# SCH_RAM-Module-Dual-IS66-DDR4_2026-05-29.net
KiCad netlist of a schematic drawn in EasyEDA
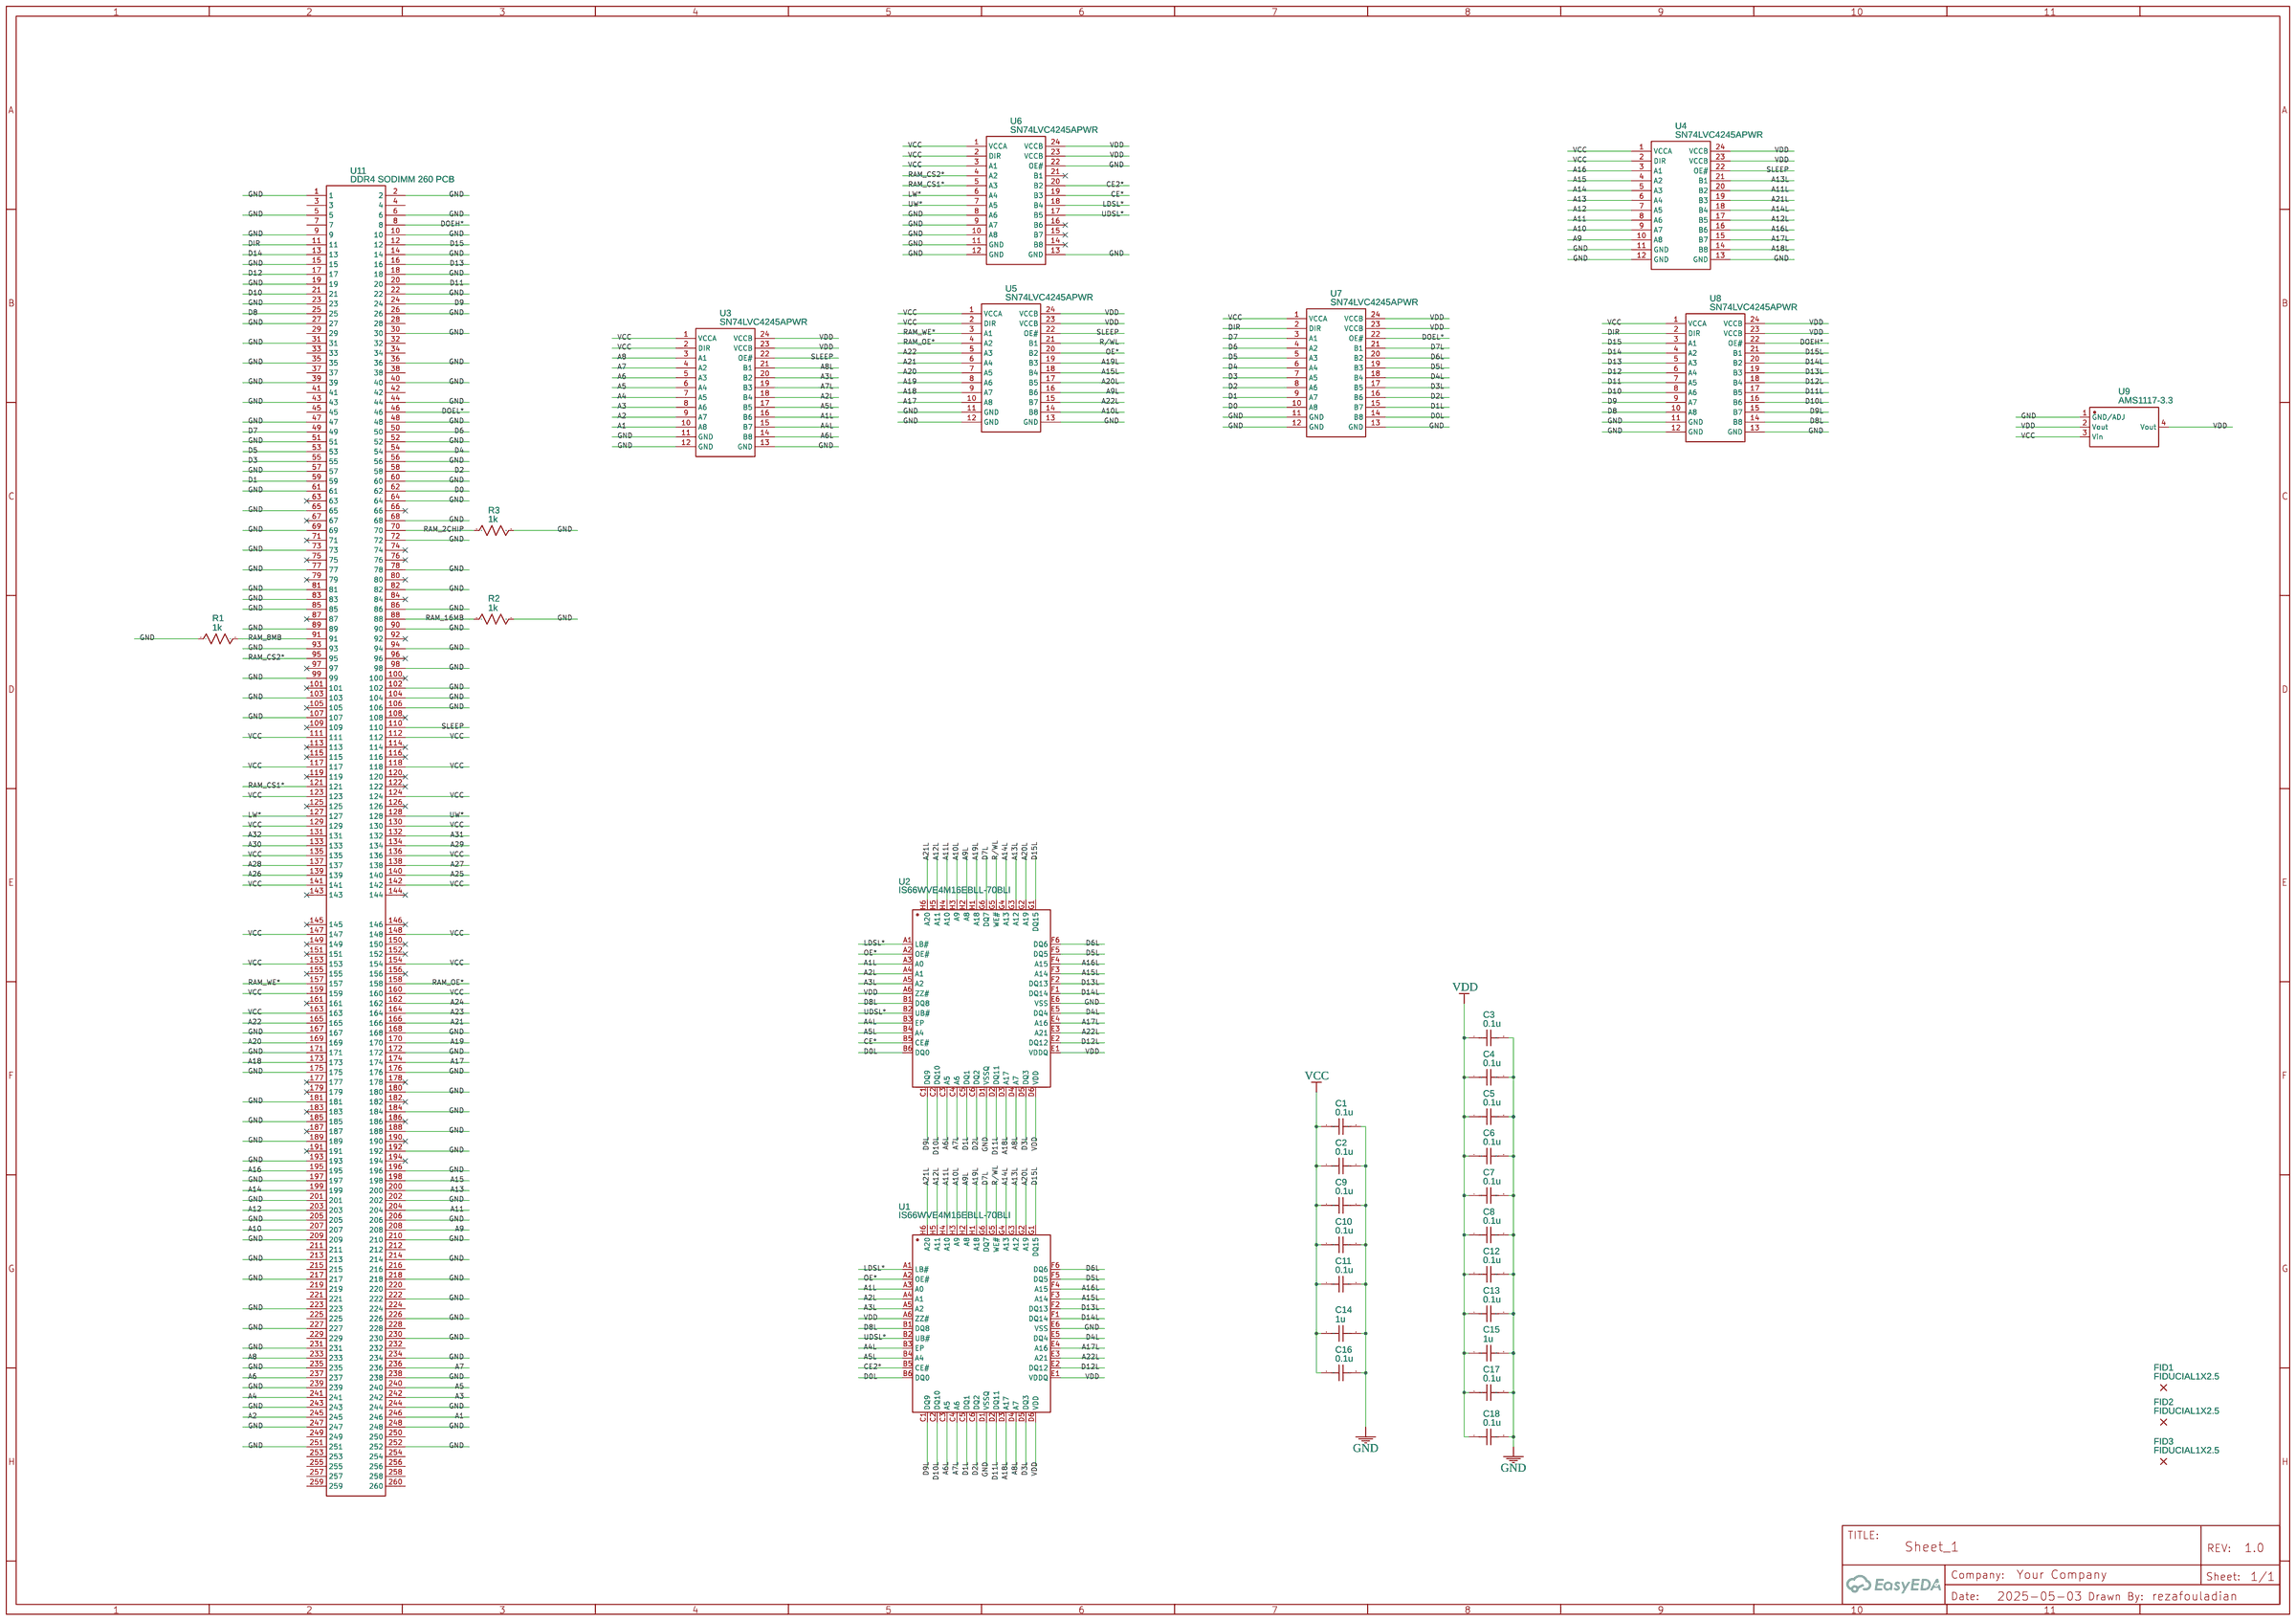
[diagram p0: schematic sheet]

(export (version "E")
  (design (tool "Eeschema 10.0.6"))
  (components
    (comp (ref "C1") (value "0.1u") (libsource (lib "") (part "C_0402_US")))
    (comp (ref "C2") (value "0.1u") (libsource (lib "") (part "C_0402_US")))
    (comp (ref "C3") (value "0.1u") (libsource (lib "") (part "C_0402_US")))
    (comp (ref "C4") (value "0.1u") (libsource (lib "") (part "C_0402_US")))
    (comp (ref "C5") (value "0.1u") (libsource (lib "") (part "C_0402_US")))
    (comp (ref "C6") (value "0.1u") (libsource (lib "") (part "C_0402_US")))
    (comp (ref "C7") (value "0.1u") (libsource (lib "") (part "C_0402_US")))
    (comp (ref "C8") (value "0.1u") (libsource (lib "") (part "C_0402_US")))
    (comp (ref "C9") (value "0.1u") (libsource (lib "") (part "C_0402_US")))
    (comp (ref "C10") (value "0.1u") (libsource (lib "") (part "C_0402_US")))
    (comp (ref "C11") (value "0.1u") (libsource (lib "") (part "C_0402_US")))
    (comp (ref "C12") (value "0.1u") (libsource (lib "") (part "C_0402_US")))
    (comp (ref "C13") (value "0.1u") (libsource (lib "") (part "C_0402_US")))
    (comp (ref "C14") (value "1u") (libsource (lib "") (part "C_0805_US")))
    (comp (ref "C15") (value "1u") (libsource (lib "") (part "C_0805_US")))
    (comp (ref "C16") (value "0.1u") (libsource (lib "") (part "C_0402_US")))
    (comp (ref "C17") (value "0.1u") (libsource (lib "") (part "C_0402_US")))
    (comp (ref "C18") (value "0.1u") (libsource (lib "") (part "C_0402_US")))
    (comp (ref "FID1") (value "FIDUCIAL1X2.5") (libsource (lib "") (part "FIDUCIAL1X2.5")))
    (comp (ref "FID2") (value "FIDUCIAL1X2.5") (libsource (lib "") (part "FIDUCIAL1X2.5")))
    (comp (ref "FID3") (value "FIDUCIAL1X2.5") (libsource (lib "") (part "FIDUCIAL1X2.5")))
    (comp (ref "R1") (value "1k") (libsource (lib "") (part "R_0402_US")))
    (comp (ref "R2") (value "1k") (libsource (lib "") (part "R_0402_US")))
    (comp (ref "R3") (value "1k") (libsource (lib "") (part "R_0402_US")))
    (comp (ref "U1")
      (value "IS66WVE4M16EBLL-70BLI")
      (fields (field (name "Manufacturer") "ISSI(美国芯成)"))
      (libsource (lib "") (part "IS66WVE4M16EBLL-70BLI"))
    )
    (comp (ref "U2")
      (value "IS66WVE4M16EBLL-70BLI")
      (fields (field (name "Manufacturer") "ISSI(美国芯成)"))
      (libsource (lib "") (part "IS66WVE4M16EBLL-70BLI"))
    )
    (comp (ref "U3")
      (value "SN74LVC4245APWR")
      (fields (field (name "Manufacturer") "TI(德州仪器)"))
      (libsource (lib "") (part "SN74LVC4245APWR"))
    )
    (comp (ref "U4")
      (value "SN74LVC4245APWR")
      (fields (field (name "Manufacturer") "TI(德州仪器)"))
      (libsource (lib "") (part "SN74LVC4245APWR"))
    )
    (comp (ref "U5")
      (value "SN74LVC4245APWR")
      (fields (field (name "Manufacturer") "TI(德州仪器)"))
      (libsource (lib "") (part "SN74LVC4245APWR"))
    )
    (comp (ref "U6")
      (value "SN74LVC4245APWR")
      (fields (field (name "Manufacturer") "TI(德州仪器)"))
      (libsource (lib "") (part "SN74LVC4245APWR"))
    )
    (comp (ref "U7")
      (value "SN74LVC4245APWR")
      (fields (field (name "Manufacturer") "TI(德州仪器)"))
      (libsource (lib "") (part "SN74LVC4245APWR"))
    )
    (comp (ref "U8")
      (value "SN74LVC4245APWR")
      (fields (field (name "Manufacturer") "TI(德州仪器)"))
      (libsource (lib "") (part "SN74LVC4245APWR"))
    )
    (comp (ref "U9")
      (value "AMS1117-3.3")
      (fields (field (name "Manufacturer") "AMS"))
      (libsource (lib "") (part "AMS1117-3.3"))
    )
    (comp (ref "U11")
      (value "DDR4 SODIMM 260 PCB")
      (fields (field (name "Manufacturer Part") "DDR4_SODIMM_260"))
      (libsource (lib "") (part "DDR4 SODIMM 260 PCB"))
    )
  )
  (nets
    (net (code "1") (name "/A1") (class "Default")
      (node (ref "U11") (pin "246") (pinfunction "246_246") (pintype "unspecified"))
      (node (ref "U3") (pin "10") (pinfunction "A8_10") (pintype "unspecified"))
    )
    (net (code "2") (name "/A1L") (class "Default")
      (node (ref "U1") (pin "A3") (pinfunction "A0_A3") (pintype "unspecified"))
      (node (ref "U2") (pin "A3") (pinfunction "A0_A3") (pintype "unspecified"))
      (node (ref "U3") (pin "16") (pinfunction "B6_16") (pintype "unspecified"))
    )
    (net (code "3") (name "/A2") (class "Default")
      (node (ref "U11") (pin "245") (pinfunction "245_245") (pintype "unspecified"))
      (node (ref "U3") (pin "9") (pinfunction "A7_9") (pintype "unspecified"))
    )
    (net (code "4") (name "/A2L") (class "Default")
      (node (ref "U1") (pin "A4") (pinfunction "A1_A4") (pintype "unspecified"))
      (node (ref "U2") (pin "A4") (pinfunction "A1_A4") (pintype "unspecified"))
      (node (ref "U3") (pin "18") (pinfunction "B4_18") (pintype "unspecified"))
    )
    (net (code "5") (name "/A3") (class "Default")
      (node (ref "U11") (pin "242") (pinfunction "242_242") (pintype "unspecified"))
      (node (ref "U3") (pin "8") (pinfunction "A6_8") (pintype "unspecified"))
    )
    (net (code "6") (name "/A3L") (class "Default")
      (node (ref "U1") (pin "A5") (pinfunction "A2_A5") (pintype "unspecified"))
      (node (ref "U2") (pin "A5") (pinfunction "A2_A5") (pintype "unspecified"))
      (node (ref "U3") (pin "20") (pinfunction "B2_20") (pintype "unspecified"))
    )
    (net (code "7") (name "/A4") (class "Default")
      (node (ref "U11") (pin "241") (pinfunction "241_241") (pintype "unspecified"))
      (node (ref "U3") (pin "7") (pinfunction "A5_7") (pintype "unspecified"))
    )
    (net (code "8") (name "/A4L") (class "Default")
      (node (ref "U1") (pin "B3") (pinfunction "EP_B3") (pintype "unspecified"))
      (node (ref "U2") (pin "B3") (pinfunction "EP_B3") (pintype "unspecified"))
      (node (ref "U3") (pin "15") (pinfunction "B7_15") (pintype "unspecified"))
    )
    (net (code "9") (name "/A5") (class "Default")
      (node (ref "U11") (pin "240") (pinfunction "240_240") (pintype "unspecified"))
      (node (ref "U3") (pin "6") (pinfunction "A4_6") (pintype "unspecified"))
    )
    (net (code "10") (name "/A5L") (class "Default")
      (node (ref "U1") (pin "B4") (pinfunction "A4_B4") (pintype "unspecified"))
      (node (ref "U2") (pin "B4") (pinfunction "A4_B4") (pintype "unspecified"))
      (node (ref "U3") (pin "17") (pinfunction "B5_17") (pintype "unspecified"))
    )
    (net (code "11") (name "/A6") (class "Default")
      (node (ref "U11") (pin "237") (pinfunction "237_237") (pintype "unspecified"))
      (node (ref "U3") (pin "5") (pinfunction "A3_5") (pintype "unspecified"))
    )
    (net (code "12") (name "/A6L") (class "Default")
      (node (ref "U1") (pin "C3") (pinfunction "A5_C3") (pintype "unspecified"))
      (node (ref "U2") (pin "C3") (pinfunction "A5_C3") (pintype "unspecified"))
      (node (ref "U3") (pin "14") (pinfunction "B8_14") (pintype "unspecified"))
    )
    (net (code "13") (name "/A7") (class "Default")
      (node (ref "U11") (pin "236") (pinfunction "236_236") (pintype "unspecified"))
      (node (ref "U3") (pin "4") (pinfunction "A2_4") (pintype "unspecified"))
    )
    (net (code "14") (name "/A7L") (class "Default")
      (node (ref "U1") (pin "C4") (pinfunction "A6_C4") (pintype "unspecified"))
      (node (ref "U2") (pin "C4") (pinfunction "A6_C4") (pintype "unspecified"))
      (node (ref "U3") (pin "19") (pinfunction "B3_19") (pintype "unspecified"))
    )
    (net (code "15") (name "/A8") (class "Default")
      (node (ref "U11") (pin "233") (pinfunction "233_233") (pintype "unspecified"))
      (node (ref "U3") (pin "3") (pinfunction "A1_3") (pintype "unspecified"))
    )
    (net (code "16") (name "/A8L") (class "Default")
      (node (ref "U1") (pin "D4") (pinfunction "A7_D4") (pintype "unspecified"))
      (node (ref "U2") (pin "D4") (pinfunction "A7_D4") (pintype "unspecified"))
      (node (ref "U3") (pin "21") (pinfunction "B1_21") (pintype "unspecified"))
    )
    (net (code "17") (name "/A9") (class "Default")
      (node (ref "U11") (pin "208") (pinfunction "208_208") (pintype "unspecified"))
      (node (ref "U4") (pin "10") (pinfunction "A8_10") (pintype "unspecified"))
    )
    (net (code "18") (name "/A9L") (class "Default")
      (node (ref "U1") (pin "H2") (pinfunction "A8_H2") (pintype "unspecified"))
      (node (ref "U2") (pin "H2") (pinfunction "A8_H2") (pintype "unspecified"))
      (node (ref "U5") (pin "16") (pinfunction "B6_16") (pintype "unspecified"))
    )
    (net (code "19") (name "/A10") (class "Default")
      (node (ref "U11") (pin "207") (pinfunction "207_207") (pintype "unspecified"))
      (node (ref "U4") (pin "9") (pinfunction "A7_9") (pintype "unspecified"))
    )
    (net (code "20") (name "/A10L") (class "Default")
      (node (ref "U1") (pin "H3") (pinfunction "A9_H3") (pintype "unspecified"))
      (node (ref "U2") (pin "H3") (pinfunction "A9_H3") (pintype "unspecified"))
      (node (ref "U5") (pin "14") (pinfunction "B8_14") (pintype "unspecified"))
    )
    (net (code "21") (name "/A11") (class "Default")
      (node (ref "U11") (pin "204") (pinfunction "204_204") (pintype "unspecified"))
      (node (ref "U4") (pin "8") (pinfunction "A6_8") (pintype "unspecified"))
    )
    (net (code "22") (name "/A11L") (class "Default")
      (node (ref "U1") (pin "H4") (pinfunction "A10_H4") (pintype "unspecified"))
      (node (ref "U2") (pin "H4") (pinfunction "A10_H4") (pintype "unspecified"))
      (node (ref "U4") (pin "20") (pinfunction "B2_20") (pintype "unspecified"))
    )
    (net (code "23") (name "/A12") (class "Default")
      (node (ref "U11") (pin "203") (pinfunction "203_203") (pintype "unspecified"))
      (node (ref "U4") (pin "7") (pinfunction "A5_7") (pintype "unspecified"))
    )
    (net (code "24") (name "/A12L") (class "Default")
      (node (ref "U1") (pin "H5") (pinfunction "A11_H5") (pintype "unspecified"))
      (node (ref "U2") (pin "H5") (pinfunction "A11_H5") (pintype "unspecified"))
      (node (ref "U4") (pin "17") (pinfunction "B5_17") (pintype "unspecified"))
    )
    (net (code "25") (name "/A13") (class "Default")
      (node (ref "U11") (pin "200") (pinfunction "200_200") (pintype "unspecified"))
      (node (ref "U4") (pin "6") (pinfunction "A4_6") (pintype "unspecified"))
    )
    (net (code "26") (name "/A13L") (class "Default")
      (node (ref "U1") (pin "G3") (pinfunction "A12_G3") (pintype "unspecified"))
      (node (ref "U2") (pin "G3") (pinfunction "A12_G3") (pintype "unspecified"))
      (node (ref "U4") (pin "21") (pinfunction "B1_21") (pintype "unspecified"))
    )
    (net (code "27") (name "/A14") (class "Default")
      (node (ref "U11") (pin "199") (pinfunction "199_199") (pintype "unspecified"))
      (node (ref "U4") (pin "5") (pinfunction "A3_5") (pintype "unspecified"))
    )
    (net (code "28") (name "/A14L") (class "Default")
      (node (ref "U1") (pin "G4") (pinfunction "A13_G4") (pintype "unspecified"))
      (node (ref "U2") (pin "G4") (pinfunction "A13_G4") (pintype "unspecified"))
      (node (ref "U4") (pin "18") (pinfunction "B4_18") (pintype "unspecified"))
    )
    (net (code "29") (name "/A15") (class "Default")
      (node (ref "U11") (pin "198") (pinfunction "198_198") (pintype "unspecified"))
      (node (ref "U4") (pin "4") (pinfunction "A2_4") (pintype "unspecified"))
    )
    (net (code "30") (name "/A15L") (class "Default")
      (node (ref "U1") (pin "F3") (pinfunction "A14_F3") (pintype "unspecified"))
      (node (ref "U2") (pin "F3") (pinfunction "A14_F3") (pintype "unspecified"))
      (node (ref "U5") (pin "18") (pinfunction "B4_18") (pintype "unspecified"))
    )
    (net (code "31") (name "/A16") (class "Default")
      (node (ref "U11") (pin "195") (pinfunction "195_195") (pintype "unspecified"))
      (node (ref "U4") (pin "3") (pinfunction "A1_3") (pintype "unspecified"))
    )
    (net (code "32") (name "/A16L") (class "Default")
      (node (ref "U1") (pin "F4") (pinfunction "A15_F4") (pintype "unspecified"))
      (node (ref "U2") (pin "F4") (pinfunction "A15_F4") (pintype "unspecified"))
      (node (ref "U4") (pin "16") (pinfunction "B6_16") (pintype "unspecified"))
    )
    (net (code "33") (name "/A17") (class "Default")
      (node (ref "U11") (pin "174") (pinfunction "174_174") (pintype "unspecified"))
      (node (ref "U5") (pin "10") (pinfunction "A8_10") (pintype "unspecified"))
    )
    (net (code "34") (name "/A17L") (class "Default")
      (node (ref "U1") (pin "E4") (pinfunction "A16_E4") (pintype "unspecified"))
      (node (ref "U2") (pin "E4") (pinfunction "A16_E4") (pintype "unspecified"))
      (node (ref "U4") (pin "15") (pinfunction "B7_15") (pintype "unspecified"))
    )
    (net (code "35") (name "/A18") (class "Default")
      (node (ref "U11") (pin "173") (pinfunction "173_173") (pintype "unspecified"))
      (node (ref "U5") (pin "9") (pinfunction "A7_9") (pintype "unspecified"))
    )
    (net (code "36") (name "/A18L") (class "Default")
      (node (ref "U1") (pin "D3") (pinfunction "A17_D3") (pintype "unspecified"))
      (node (ref "U2") (pin "D3") (pinfunction "A17_D3") (pintype "unspecified"))
      (node (ref "U4") (pin "14") (pinfunction "B8_14") (pintype "unspecified"))
    )
    (net (code "37") (name "/A19") (class "Default")
      (node (ref "U11") (pin "170") (pinfunction "170_170") (pintype "unspecified"))
      (node (ref "U5") (pin "8") (pinfunction "A6_8") (pintype "unspecified"))
    )
    (net (code "38") (name "/A19L") (class "Default")
      (node (ref "U1") (pin "H1") (pinfunction "A18_H1") (pintype "unspecified"))
      (node (ref "U2") (pin "H1") (pinfunction "A18_H1") (pintype "unspecified"))
      (node (ref "U5") (pin "19") (pinfunction "B3_19") (pintype "unspecified"))
    )
    (net (code "39") (name "/A20") (class "Default")
      (node (ref "U11") (pin "169") (pinfunction "169_169") (pintype "unspecified"))
      (node (ref "U5") (pin "7") (pinfunction "A5_7") (pintype "unspecified"))
    )
    (net (code "40") (name "/A20L") (class "Default")
      (node (ref "U1") (pin "G2") (pinfunction "A19_G2") (pintype "unspecified"))
      (node (ref "U2") (pin "G2") (pinfunction "A19_G2") (pintype "unspecified"))
      (node (ref "U5") (pin "17") (pinfunction "B5_17") (pintype "unspecified"))
    )
    (net (code "41") (name "/A21") (class "Default")
      (node (ref "U11") (pin "166") (pinfunction "166_166") (pintype "unspecified"))
      (node (ref "U5") (pin "6") (pinfunction "A4_6") (pintype "unspecified"))
    )
    (net (code "42") (name "/A21L") (class "Default")
      (node (ref "U1") (pin "H6") (pinfunction "A20_H6") (pintype "unspecified"))
      (node (ref "U2") (pin "H6") (pinfunction "A20_H6") (pintype "unspecified"))
      (node (ref "U4") (pin "19") (pinfunction "B3_19") (pintype "unspecified"))
    )
    (net (code "43") (name "/A22") (class "Default")
      (node (ref "U11") (pin "165") (pinfunction "165_165") (pintype "unspecified"))
      (node (ref "U5") (pin "5") (pinfunction "A3_5") (pintype "unspecified"))
    )
    (net (code "44") (name "/A22L") (class "Default")
      (node (ref "U1") (pin "E3") (pinfunction "A21_E3") (pintype "unspecified"))
      (node (ref "U2") (pin "E3") (pinfunction "A21_E3") (pintype "unspecified"))
      (node (ref "U5") (pin "15") (pinfunction "B7_15") (pintype "unspecified"))
    )
    (net (code "45") (name "/A23") (class "Default")
      (node (ref "U11") (pin "164") (pinfunction "164_164") (pintype "unspecified"))
    )
    (net (code "46") (name "/A24") (class "Default")
      (node (ref "U11") (pin "162") (pinfunction "162_162") (pintype "unspecified"))
    )
    (net (code "47") (name "/A25") (class "Default")
      (node (ref "U11") (pin "140") (pinfunction "140_140") (pintype "unspecified"))
    )
    (net (code "48") (name "/A26") (class "Default")
      (node (ref "U11") (pin "139") (pinfunction "139_139") (pintype "unspecified"))
    )
    (net (code "49") (name "/A27") (class "Default")
      (node (ref "U11") (pin "138") (pinfunction "138_138") (pintype "unspecified"))
    )
    (net (code "50") (name "/A28") (class "Default")
      (node (ref "U11") (pin "137") (pinfunction "137_137") (pintype "unspecified"))
    )
    (net (code "51") (name "/A29") (class "Default")
      (node (ref "U11") (pin "134") (pinfunction "134_134") (pintype "unspecified"))
    )
    (net (code "52") (name "/A30") (class "Default")
      (node (ref "U11") (pin "133") (pinfunction "133_133") (pintype "unspecified"))
    )
    (net (code "53") (name "/A31") (class "Default")
      (node (ref "U11") (pin "132") (pinfunction "132_132") (pintype "unspecified"))
    )
    (net (code "54") (name "/A32") (class "Default")
      (node (ref "U11") (pin "131") (pinfunction "131_131") (pintype "unspecified"))
    )
    (net (code "55") (name "/CE*") (class "Default")
      (node (ref "U2") (pin "B5") (pinfunction "CE#_B5") (pintype "unspecified"))
      (node (ref "U6") (pin "19") (pinfunction "B3_19") (pintype "unspecified"))
    )
    (net (code "56") (name "/CE2*") (class "Default")
      (node (ref "U1") (pin "B5") (pinfunction "CE#_B5") (pintype "unspecified"))
      (node (ref "U6") (pin "20") (pinfunction "B2_20") (pintype "unspecified"))
    )
    (net (code "57") (name "/D0") (class "Default")
      (node (ref "U11") (pin "62") (pinfunction "62_62") (pintype "unspecified"))
      (node (ref "U7") (pin "10") (pinfunction "A8_10") (pintype "unspecified"))
    )
    (net (code "58") (name "/D0L") (class "Default")
      (node (ref "U1") (pin "B6") (pinfunction "DQ0_B6") (pintype "unspecified"))
      (node (ref "U2") (pin "B6") (pinfunction "DQ0_B6") (pintype "unspecified"))
      (node (ref "U7") (pin "14") (pinfunction "B8_14") (pintype "unspecified"))
    )
    (net (code "59") (name "/D1") (class "Default")
      (node (ref "U11") (pin "59") (pinfunction "59_59") (pintype "unspecified"))
      (node (ref "U7") (pin "9") (pinfunction "A7_9") (pintype "unspecified"))
    )
    (net (code "60") (name "/D1L") (class "Default")
      (node (ref "U1") (pin "C5") (pinfunction "DQ1_C5") (pintype "unspecified"))
      (node (ref "U2") (pin "C5") (pinfunction "DQ1_C5") (pintype "unspecified"))
      (node (ref "U7") (pin "15") (pinfunction "B7_15") (pintype "unspecified"))
    )
    (net (code "61") (name "/D2") (class "Default")
      (node (ref "U11") (pin "58") (pinfunction "58_58") (pintype "unspecified"))
      (node (ref "U7") (pin "8") (pinfunction "A6_8") (pintype "unspecified"))
    )
    (net (code "62") (name "/D2L") (class "Default")
      (node (ref "U1") (pin "C6") (pinfunction "DQ2_C6") (pintype "unspecified"))
      (node (ref "U2") (pin "C6") (pinfunction "DQ2_C6") (pintype "unspecified"))
      (node (ref "U7") (pin "16") (pinfunction "B6_16") (pintype "unspecified"))
    )
    (net (code "63") (name "/D3") (class "Default")
      (node (ref "U11") (pin "55") (pinfunction "55_55") (pintype "unspecified"))
      (node (ref "U7") (pin "7") (pinfunction "A5_7") (pintype "unspecified"))
    )
    (net (code "64") (name "/D3L") (class "Default")
      (node (ref "U1") (pin "D5") (pinfunction "DQ3_D5") (pintype "unspecified"))
      (node (ref "U2") (pin "D5") (pinfunction "DQ3_D5") (pintype "unspecified"))
      (node (ref "U7") (pin "17") (pinfunction "B5_17") (pintype "unspecified"))
    )
    (net (code "65") (name "/D4") (class "Default")
      (node (ref "U11") (pin "54") (pinfunction "54_54") (pintype "unspecified"))
      (node (ref "U7") (pin "6") (pinfunction "A4_6") (pintype "unspecified"))
    )
    (net (code "66") (name "/D4L") (class "Default")
      (node (ref "U1") (pin "E5") (pinfunction "DQ4_E5") (pintype "unspecified"))
      (node (ref "U2") (pin "E5") (pinfunction "DQ4_E5") (pintype "unspecified"))
      (node (ref "U7") (pin "18") (pinfunction "B4_18") (pintype "unspecified"))
    )
    (net (code "67") (name "/D5") (class "Default")
      (node (ref "U11") (pin "53") (pinfunction "53_53") (pintype "unspecified"))
      (node (ref "U7") (pin "5") (pinfunction "A3_5") (pintype "unspecified"))
    )
    (net (code "68") (name "/D5L") (class "Default")
      (node (ref "U1") (pin "F5") (pinfunction "DQ5_F5") (pintype "unspecified"))
      (node (ref "U2") (pin "F5") (pinfunction "DQ5_F5") (pintype "unspecified"))
      (node (ref "U7") (pin "19") (pinfunction "B3_19") (pintype "unspecified"))
    )
    (net (code "69") (name "/D6") (class "Default")
      (node (ref "U11") (pin "50") (pinfunction "50_50") (pintype "unspecified"))
      (node (ref "U7") (pin "4") (pinfunction "A2_4") (pintype "unspecified"))
    )
    (net (code "70") (name "/D6L") (class "Default")
      (node (ref "U1") (pin "F6") (pinfunction "DQ6_F6") (pintype "unspecified"))
      (node (ref "U2") (pin "F6") (pinfunction "DQ6_F6") (pintype "unspecified"))
      (node (ref "U7") (pin "20") (pinfunction "B2_20") (pintype "unspecified"))
    )
    (net (code "71") (name "/D7") (class "Default")
      (node (ref "U11") (pin "49") (pinfunction "49_49") (pintype "unspecified"))
      (node (ref "U7") (pin "3") (pinfunction "A1_3") (pintype "unspecified"))
    )
    (net (code "72") (name "/D7L") (class "Default")
      (node (ref "U1") (pin "G6") (pinfunction "DQ7_G6") (pintype "unspecified"))
      (node (ref "U2") (pin "G6") (pinfunction "DQ7_G6") (pintype "unspecified"))
      (node (ref "U7") (pin "21") (pinfunction "B1_21") (pintype "unspecified"))
    )
    (net (code "73") (name "/D8") (class "Default")
      (node (ref "U11") (pin "25") (pinfunction "25_25") (pintype "unspecified"))
      (node (ref "U8") (pin "10") (pinfunction "A8_10") (pintype "unspecified"))
    )
    (net (code "74") (name "/D8L") (class "Default")
      (node (ref "U1") (pin "B1") (pinfunction "DQ8_B1") (pintype "unspecified"))
      (node (ref "U2") (pin "B1") (pinfunction "DQ8_B1") (pintype "unspecified"))
      (node (ref "U8") (pin "14") (pinfunction "B8_14") (pintype "unspecified"))
    )
    (net (code "75") (name "/D9") (class "Default")
      (node (ref "U11") (pin "24") (pinfunction "24_24") (pintype "unspecified"))
      (node (ref "U8") (pin "9") (pinfunction "A7_9") (pintype "unspecified"))
    )
    (net (code "76") (name "/D9L") (class "Default")
      (node (ref "U1") (pin "C1") (pinfunction "DQ9_C1") (pintype "unspecified"))
      (node (ref "U2") (pin "C1") (pinfunction "DQ9_C1") (pintype "unspecified"))
      (node (ref "U8") (pin "15") (pinfunction "B7_15") (pintype "unspecified"))
    )
    (net (code "77") (name "/D10") (class "Default")
      (node (ref "U11") (pin "21") (pinfunction "21_21") (pintype "unspecified"))
      (node (ref "U8") (pin "8") (pinfunction "A6_8") (pintype "unspecified"))
    )
    (net (code "78") (name "/D10L") (class "Default")
      (node (ref "U1") (pin "C2") (pinfunction "DQ10_C2") (pintype "unspecified"))
      (node (ref "U2") (pin "C2") (pinfunction "DQ10_C2") (pintype "unspecified"))
      (node (ref "U8") (pin "16") (pinfunction "B6_16") (pintype "unspecified"))
    )
    (net (code "79") (name "/D11") (class "Default")
      (node (ref "U11") (pin "20") (pinfunction "20_20") (pintype "unspecified"))
      (node (ref "U8") (pin "7") (pinfunction "A5_7") (pintype "unspecified"))
    )
    (net (code "80") (name "/D11L") (class "Default")
      (node (ref "U1") (pin "D2") (pinfunction "DQ11_D2") (pintype "unspecified"))
      (node (ref "U2") (pin "D2") (pinfunction "DQ11_D2") (pintype "unspecified"))
      (node (ref "U8") (pin "17") (pinfunction "B5_17") (pintype "unspecified"))
    )
    (net (code "81") (name "/D12") (class "Default")
      (node (ref "U11") (pin "17") (pinfunction "17_17") (pintype "unspecified"))
      (node (ref "U8") (pin "6") (pinfunction "A4_6") (pintype "unspecified"))
    )
    (net (code "82") (name "/D12L") (class "Default")
      (node (ref "U1") (pin "E2") (pinfunction "DQ12_E2") (pintype "unspecified"))
      (node (ref "U2") (pin "E2") (pinfunction "DQ12_E2") (pintype "unspecified"))
      (node (ref "U8") (pin "18") (pinfunction "B4_18") (pintype "unspecified"))
    )
    (net (code "83") (name "/D13") (class "Default")
      (node (ref "U11") (pin "16") (pinfunction "16_16") (pintype "unspecified"))
      (node (ref "U8") (pin "5") (pinfunction "A3_5") (pintype "unspecified"))
    )
    (net (code "84") (name "/D13L") (class "Default")
      (node (ref "U1") (pin "F2") (pinfunction "DQ13_F2") (pintype "unspecified"))
      (node (ref "U2") (pin "F2") (pinfunction "DQ13_F2") (pintype "unspecified"))
      (node (ref "U8") (pin "19") (pinfunction "B3_19") (pintype "unspecified"))
    )
    (net (code "85") (name "/D14") (class "Default")
      (node (ref "U11") (pin "13") (pinfunction "13_13") (pintype "unspecified"))
      (node (ref "U8") (pin "4") (pinfunction "A2_4") (pintype "unspecified"))
    )
    (net (code "86") (name "/D14L") (class "Default")
      (node (ref "U1") (pin "F1") (pinfunction "DQ14_F1") (pintype "unspecified"))
      (node (ref "U2") (pin "F1") (pinfunction "DQ14_F1") (pintype "unspecified"))
      (node (ref "U8") (pin "20") (pinfunction "B2_20") (pintype "unspecified"))
    )
    (net (code "87") (name "/D15") (class "Default")
      (node (ref "U11") (pin "12") (pinfunction "12_12") (pintype "unspecified"))
      (node (ref "U8") (pin "3") (pinfunction "A1_3") (pintype "unspecified"))
    )
    (net (code "88") (name "/D15L") (class "Default")
      (node (ref "U1") (pin "G1") (pinfunction "DQ15_G1") (pintype "unspecified"))
      (node (ref "U2") (pin "G1") (pinfunction "DQ15_G1") (pintype "unspecified"))
      (node (ref "U8") (pin "21") (pinfunction "B1_21") (pintype "unspecified"))
    )
    (net (code "89") (name "/DIR") (class "Default")
      (node (ref "U11") (pin "11") (pinfunction "11_11") (pintype "unspecified"))
      (node (ref "U7") (pin "2") (pinfunction "DIR_2") (pintype "unspecified"))
      (node (ref "U8") (pin "2") (pinfunction "DIR_2") (pintype "unspecified"))
    )
    (net (code "90") (name "/DOEH*") (class "Default")
      (node (ref "U11") (pin "8") (pinfunction "8_8") (pintype "unspecified"))
      (node (ref "U8") (pin "22") (pinfunction "OE#_22") (pintype "unspecified"))
    )
    (net (code "91") (name "/DOEL*") (class "Default")
      (node (ref "U11") (pin "46") (pinfunction "46_46") (pintype "unspecified"))
      (node (ref "U7") (pin "22") (pinfunction "OE#_22") (pintype "unspecified"))
    )
    (net (code "92") (name "/LDSL*") (class "Default")
      (node (ref "U1") (pin "A1") (pinfunction "LB#_A1") (pintype "unspecified"))
      (node (ref "U2") (pin "A1") (pinfunction "LB#_A1") (pintype "unspecified"))
      (node (ref "U6") (pin "18") (pinfunction "B4_18") (pintype "unspecified"))
    )
    (net (code "93") (name "/LW*") (class "Default")
      (node (ref "U11") (pin "127") (pinfunction "127_127") (pintype "unspecified"))
      (node (ref "U6") (pin "6") (pinfunction "A4_6") (pintype "unspecified"))
    )
    (net (code "94") (name "/OE*") (class "Default")
      (node (ref "U1") (pin "A2") (pinfunction "OE#_A2") (pintype "unspecified"))
      (node (ref "U2") (pin "A2") (pinfunction "OE#_A2") (pintype "unspecified"))
      (node (ref "U5") (pin "20") (pinfunction "B2_20") (pintype "unspecified"))
    )
    (net (code "95") (name "/RAM_2CHIP") (class "Default")
      (node (ref "R3") (pin "1") (pinfunction "1_1") (pintype "unspecified"))
      (node (ref "U11") (pin "70") (pinfunction "70_70") (pintype "unspecified"))
    )
    (net (code "96") (name "/RAM_8MB") (class "Default")
      (node (ref "R1") (pin "2") (pinfunction "2_2") (pintype "unspecified"))
      (node (ref "U11") (pin "91") (pinfunction "91_91") (pintype "unspecified"))
    )
    (net (code "97") (name "/RAM_16MB") (class "Default")
      (node (ref "R2") (pin "1") (pinfunction "1_1") (pintype "unspecified"))
      (node (ref "U11") (pin "88") (pinfunction "88_88") (pintype "unspecified"))
    )
    (net (code "98") (name "/RAM_CS1*") (class "Default")
      (node (ref "U11") (pin "121") (pinfunction "121_121") (pintype "unspecified"))
      (node (ref "U6") (pin "5") (pinfunction "A3_5") (pintype "unspecified"))
    )
    (net (code "99") (name "/RAM_CS2*") (class "Default")
      (node (ref "U11") (pin "95") (pinfunction "95_95") (pintype "unspecified"))
      (node (ref "U6") (pin "4") (pinfunction "A2_4") (pintype "unspecified"))
    )
    (net (code "100") (name "/RAM_OE*") (class "Default")
      (node (ref "U11") (pin "158") (pinfunction "158_158") (pintype "unspecified"))
      (node (ref "U5") (pin "4") (pinfunction "A2_4") (pintype "unspecified"))
    )
    (net (code "101") (name "/RAM_WE*") (class "Default")
      (node (ref "U11") (pin "157") (pinfunction "157_157") (pintype "unspecified"))
      (node (ref "U5") (pin "3") (pinfunction "A1_3") (pintype "unspecified"))
    )
    (net (code "102") (name "/R{slash}WL") (class "Default")
      (node (ref "U1") (pin "G5") (pinfunction "WE#_G5") (pintype "unspecified"))
      (node (ref "U2") (pin "G5") (pinfunction "WE#_G5") (pintype "unspecified"))
      (node (ref "U5") (pin "21") (pinfunction "B1_21") (pintype "unspecified"))
    )
    (net (code "103") (name "/SLEEP") (class "Default")
      (node (ref "U11") (pin "110") (pinfunction "110_110") (pintype "unspecified"))
      (node (ref "U3") (pin "22") (pinfunction "OE#_22") (pintype "unspecified"))
      (node (ref "U4") (pin "22") (pinfunction "OE#_22") (pintype "unspecified"))
      (node (ref "U5") (pin "22") (pinfunction "OE#_22") (pintype "unspecified"))
    )
    (net (code "104") (name "/UDSL*") (class "Default")
      (node (ref "U1") (pin "B2") (pinfunction "UB#_B2") (pintype "unspecified"))
      (node (ref "U2") (pin "B2") (pinfunction "UB#_B2") (pintype "unspecified"))
      (node (ref "U6") (pin "17") (pinfunction "B5_17") (pintype "unspecified"))
    )
    (net (code "105") (name "/UW*") (class "Default")
      (node (ref "U11") (pin "128") (pinfunction "128_128") (pintype "unspecified"))
      (node (ref "U6") (pin "7") (pinfunction "A5_7") (pintype "unspecified"))
    )
    (net (code "106") (name "GND") (class "Default")
      (node (ref "C1") (pin "2") (pinfunction "2_2") (pintype "unspecified"))
      (node (ref "C10") (pin "2") (pinfunction "2_2") (pintype "unspecified"))
      (node (ref "C11") (pin "2") (pinfunction "2_2") (pintype "unspecified"))
      (node (ref "C12") (pin "2") (pinfunction "2_2") (pintype "unspecified"))
      (node (ref "C13") (pin "2") (pinfunction "2_2") (pintype "unspecified"))
      (node (ref "C14") (pin "2") (pinfunction "2_2") (pintype "unspecified"))
      (node (ref "C15") (pin "2") (pinfunction "2_2") (pintype "unspecified"))
      (node (ref "C16") (pin "2") (pinfunction "2_2") (pintype "unspecified"))
      (node (ref "C17") (pin "2") (pinfunction "2_2") (pintype "unspecified"))
      (node (ref "C18") (pin "2") (pinfunction "2_2") (pintype "unspecified"))
      (node (ref "C2") (pin "2") (pinfunction "2_2") (pintype "unspecified"))
      (node (ref "C3") (pin "2") (pinfunction "2_2") (pintype "unspecified"))
      (node (ref "C4") (pin "2") (pinfunction "2_2") (pintype "unspecified"))
      (node (ref "C5") (pin "2") (pinfunction "2_2") (pintype "unspecified"))
      (node (ref "C6") (pin "2") (pinfunction "2_2") (pintype "unspecified"))
      (node (ref "C7") (pin "2") (pinfunction "2_2") (pintype "unspecified"))
      (node (ref "C8") (pin "2") (pinfunction "2_2") (pintype "unspecified"))
      (node (ref "C9") (pin "2") (pinfunction "2_2") (pintype "unspecified"))
      (node (ref "R1") (pin "1") (pinfunction "1_1") (pintype "unspecified"))
      (node (ref "R2") (pin "2") (pinfunction "2_2") (pintype "unspecified"))
      (node (ref "R3") (pin "2") (pinfunction "2_2") (pintype "unspecified"))
      (node (ref "U1") (pin "D1") (pinfunction "VSSQ_D1") (pintype "unspecified"))
      (node (ref "U1") (pin "E6") (pinfunction "VSS_E6") (pintype "unspecified"))
      (node (ref "U11") (pin "1") (pinfunction "1_1") (pintype "unspecified"))
      (node (ref "U11") (pin "10") (pinfunction "10_10") (pintype "unspecified"))
      (node (ref "U11") (pin "102") (pinfunction "102_102") (pintype "unspecified"))
      (node (ref "U11") (pin "103") (pinfunction "103_103") (pintype "unspecified"))
      (node (ref "U11") (pin "104") (pinfunction "104_104") (pintype "unspecified"))
      (node (ref "U11") (pin "106") (pinfunction "106_106") (pintype "unspecified"))
      (node (ref "U11") (pin "107") (pinfunction "107_107") (pintype "unspecified"))
      (node (ref "U11") (pin "14") (pinfunction "14_14") (pintype "unspecified"))
      (node (ref "U11") (pin "15") (pinfunction "15_15") (pintype "unspecified"))
      (node (ref "U11") (pin "167") (pinfunction "167_167") (pintype "unspecified"))
      (node (ref "U11") (pin "168") (pinfunction "168_168") (pintype "unspecified"))
      (node (ref "U11") (pin "171") (pinfunction "171_171") (pintype "unspecified"))
      (node (ref "U11") (pin "172") (pinfunction "172_172") (pintype "unspecified"))
      (node (ref "U11") (pin "175") (pinfunction "175_175") (pintype "unspecified"))
      (node (ref "U11") (pin "176") (pinfunction "176_176") (pintype "unspecified"))
      (node (ref "U11") (pin "18") (pinfunction "18_18") (pintype "unspecified"))
      (node (ref "U11") (pin "180") (pinfunction "180_180") (pintype "unspecified"))
      (node (ref "U11") (pin "181") (pinfunction "181_181") (pintype "unspecified"))
      (node (ref "U11") (pin "184") (pinfunction "184_184") (pintype "unspecified"))
      (node (ref "U11") (pin "185") (pinfunction "185_185") (pintype "unspecified"))
      (node (ref "U11") (pin "188") (pinfunction "188_188") (pintype "unspecified"))
      (node (ref "U11") (pin "189") (pinfunction "189_189") (pintype "unspecified"))
      (node (ref "U11") (pin "19") (pinfunction "19_19") (pintype "unspecified"))
      (node (ref "U11") (pin "192") (pinfunction "192_192") (pintype "unspecified"))
      (node (ref "U11") (pin "193") (pinfunction "193_193") (pintype "unspecified"))
      (node (ref "U11") (pin "196") (pinfunction "196_196") (pintype "unspecified"))
      (node (ref "U11") (pin "197") (pinfunction "197_197") (pintype "unspecified"))
      (node (ref "U11") (pin "2") (pinfunction "2_2") (pintype "unspecified"))
      (node (ref "U11") (pin "201") (pinfunction "201_201") (pintype "unspecified"))
      (node (ref "U11") (pin "202") (pinfunction "202_202") (pintype "unspecified"))
      (node (ref "U11") (pin "205") (pinfunction "205_205") (pintype "unspecified"))
      (node (ref "U11") (pin "206") (pinfunction "206_206") (pintype "unspecified"))
      (node (ref "U11") (pin "209") (pinfunction "209_209") (pintype "unspecified"))
      (node (ref "U11") (pin "210") (pinfunction "210_210") (pintype "unspecified"))
      (node (ref "U11") (pin "213") (pinfunction "213_213") (pintype "unspecified"))
      (node (ref "U11") (pin "214") (pinfunction "214_214") (pintype "unspecified"))
      (node (ref "U11") (pin "217") (pinfunction "217_217") (pintype "unspecified"))
      (node (ref "U11") (pin "218") (pinfunction "218_218") (pintype "unspecified"))
      (node (ref "U11") (pin "22") (pinfunction "22_22") (pintype "unspecified"))
      (node (ref "U11") (pin "222") (pinfunction "222_222") (pintype "unspecified"))
      (node (ref "U11") (pin "223") (pinfunction "223_223") (pintype "unspecified"))
      (node (ref "U11") (pin "226") (pinfunction "226_226") (pintype "unspecified"))
      (node (ref "U11") (pin "227") (pinfunction "227_227") (pintype "unspecified"))
      (node (ref "U11") (pin "23") (pinfunction "23_23") (pintype "unspecified"))
      (node (ref "U11") (pin "230") (pinfunction "230_230") (pintype "unspecified"))
      (node (ref "U11") (pin "231") (pinfunction "231_231") (pintype "unspecified"))
      (node (ref "U11") (pin "234") (pinfunction "234_234") (pintype "unspecified"))
      (node (ref "U11") (pin "235") (pinfunction "235_235") (pintype "unspecified"))
      (node (ref "U11") (pin "238") (pinfunction "238_238") (pintype "unspecified"))
      (node (ref "U11") (pin "239") (pinfunction "239_239") (pintype "unspecified"))
      (node (ref "U11") (pin "243") (pinfunction "243_243") (pintype "unspecified"))
      (node (ref "U11") (pin "244") (pinfunction "244_244") (pintype "unspecified"))
      (node (ref "U11") (pin "247") (pinfunction "247_247") (pintype "unspecified"))
      (node (ref "U11") (pin "248") (pinfunction "248_248") (pintype "unspecified"))
      (node (ref "U11") (pin "251") (pinfunction "251_251") (pintype "unspecified"))
      (node (ref "U11") (pin "252") (pinfunction "252_252") (pintype "unspecified"))
      (node (ref "U11") (pin "26") (pinfunction "26_26") (pintype "unspecified"))
      (node (ref "U11") (pin "27") (pinfunction "27_27") (pintype "unspecified"))
      (node (ref "U11") (pin "30") (pinfunction "30_30") (pintype "unspecified"))
      (node (ref "U11") (pin "31") (pinfunction "31_31") (pintype "unspecified"))
      (node (ref "U11") (pin "35") (pinfunction "35_35") (pintype "unspecified"))
      (node (ref "U11") (pin "36") (pinfunction "36_36") (pintype "unspecified"))
      (node (ref "U11") (pin "39") (pinfunction "39_39") (pintype "unspecified"))
      (node (ref "U11") (pin "40") (pinfunction "40_40") (pintype "unspecified"))
      (node (ref "U11") (pin "43") (pinfunction "43_43") (pintype "unspecified"))
      (node (ref "U11") (pin "44") (pinfunction "44_44") (pintype "unspecified"))
      (node (ref "U11") (pin "47") (pinfunction "47_47") (pintype "unspecified"))
      (node (ref "U11") (pin "48") (pinfunction "48_48") (pintype "unspecified"))
      (node (ref "U11") (pin "5") (pinfunction "5_5") (pintype "unspecified"))
      (node (ref "U11") (pin "51") (pinfunction "51_51") (pintype "unspecified"))
      (node (ref "U11") (pin "52") (pinfunction "52_52") (pintype "unspecified"))
      (node (ref "U11") (pin "56") (pinfunction "56_56") (pintype "unspecified"))
      (node (ref "U11") (pin "57") (pinfunction "57_57") (pintype "unspecified"))
      (node (ref "U11") (pin "6") (pinfunction "6_6") (pintype "unspecified"))
      (node (ref "U11") (pin "60") (pinfunction "60_60") (pintype "unspecified"))
      (node (ref "U11") (pin "61") (pinfunction "61_61") (pintype "unspecified"))
      (node (ref "U11") (pin "64") (pinfunction "64_64") (pintype "unspecified"))
      (node (ref "U11") (pin "65") (pinfunction "65_65") (pintype "unspecified"))
      (node (ref "U11") (pin "68") (pinfunction "68_68") (pintype "unspecified"))
      (node (ref "U11") (pin "69") (pinfunction "69_69") (pintype "unspecified"))
      (node (ref "U11") (pin "72") (pinfunction "72_72") (pintype "unspecified"))
      (node (ref "U11") (pin "73") (pinfunction "73_73") (pintype "unspecified"))
      (node (ref "U11") (pin "77") (pinfunction "77_77") (pintype "unspecified"))
      (node (ref "U11") (pin "78") (pinfunction "78_78") (pintype "unspecified"))
      (node (ref "U11") (pin "81") (pinfunction "81_81") (pintype "unspecified"))
      (node (ref "U11") (pin "82") (pinfunction "82_82") (pintype "unspecified"))
      (node (ref "U11") (pin "83") (pinfunction "83_83") (pintype "unspecified"))
      (node (ref "U11") (pin "85") (pinfunction "85_85") (pintype "unspecified"))
      (node (ref "U11") (pin "86") (pinfunction "86_86") (pintype "unspecified"))
      (node (ref "U11") (pin "89") (pinfunction "89_89") (pintype "unspecified"))
      (node (ref "U11") (pin "9") (pinfunction "9_9") (pintype "unspecified"))
      (node (ref "U11") (pin "90") (pinfunction "90_90") (pintype "unspecified"))
      (node (ref "U11") (pin "93") (pinfunction "93_93") (pintype "unspecified"))
      (node (ref "U11") (pin "94") (pinfunction "94_94") (pintype "unspecified"))
      (node (ref "U11") (pin "98") (pinfunction "98_98") (pintype "unspecified"))
      (node (ref "U11") (pin "99") (pinfunction "99_99") (pintype "unspecified"))
      (node (ref "U2") (pin "D1") (pinfunction "VSSQ_D1") (pintype "unspecified"))
      (node (ref "U2") (pin "E6") (pinfunction "VSS_E6") (pintype "unspecified"))
      (node (ref "U3") (pin "11") (pinfunction "GND_11") (pintype "unspecified"))
      (node (ref "U3") (pin "12") (pinfunction "GND_12") (pintype "unspecified"))
      (node (ref "U3") (pin "13") (pinfunction "GND_13") (pintype "unspecified"))
      (node (ref "U4") (pin "11") (pinfunction "GND_11") (pintype "unspecified"))
      (node (ref "U4") (pin "12") (pinfunction "GND_12") (pintype "unspecified"))
      (node (ref "U4") (pin "13") (pinfunction "GND_13") (pintype "unspecified"))
      (node (ref "U5") (pin "11") (pinfunction "GND_11") (pintype "unspecified"))
      (node (ref "U5") (pin "12") (pinfunction "GND_12") (pintype "unspecified"))
      (node (ref "U5") (pin "13") (pinfunction "GND_13") (pintype "unspecified"))
      (node (ref "U6") (pin "10") (pinfunction "A8_10") (pintype "unspecified"))
      (node (ref "U6") (pin "11") (pinfunction "GND_11") (pintype "unspecified"))
      (node (ref "U6") (pin "12") (pinfunction "GND_12") (pintype "unspecified"))
      (node (ref "U6") (pin "13") (pinfunction "GND_13") (pintype "unspecified"))
      (node (ref "U6") (pin "22") (pinfunction "OE#_22") (pintype "unspecified"))
      (node (ref "U6") (pin "8") (pinfunction "A6_8") (pintype "unspecified"))
      (node (ref "U6") (pin "9") (pinfunction "A7_9") (pintype "unspecified"))
      (node (ref "U7") (pin "11") (pinfunction "GND_11") (pintype "unspecified"))
      (node (ref "U7") (pin "12") (pinfunction "GND_12") (pintype "unspecified"))
      (node (ref "U7") (pin "13") (pinfunction "GND_13") (pintype "unspecified"))
      (node (ref "U8") (pin "11") (pinfunction "GND_11") (pintype "unspecified"))
      (node (ref "U8") (pin "12") (pinfunction "GND_12") (pintype "unspecified"))
      (node (ref "U8") (pin "13") (pinfunction "GND_13") (pintype "unspecified"))
      (node (ref "U9") (pin "1") (pinfunction "GND/ADJ_1") (pintype "unspecified"))
    )
    (net (code "107") (name "VCC") (class "Default")
      (node (ref "C1") (pin "1") (pinfunction "1_1") (pintype "unspecified"))
      (node (ref "C10") (pin "1") (pinfunction "1_1") (pintype "unspecified"))
      (node (ref "C11") (pin "1") (pinfunction "1_1") (pintype "unspecified"))
      (node (ref "C14") (pin "1") (pinfunction "1_1") (pintype "unspecified"))
      (node (ref "C16") (pin "1") (pinfunction "1_1") (pintype "unspecified"))
      (node (ref "C2") (pin "1") (pinfunction "1_1") (pintype "unspecified"))
      (node (ref "C9") (pin "1") (pinfunction "1_1") (pintype "unspecified"))
      (node (ref "U11") (pin "111") (pinfunction "111_111") (pintype "unspecified"))
      (node (ref "U11") (pin "112") (pinfunction "112_112") (pintype "unspecified"))
      (node (ref "U11") (pin "117") (pinfunction "117_117") (pintype "unspecified"))
      (node (ref "U11") (pin "118") (pinfunction "118_118") (pintype "unspecified"))
      (node (ref "U11") (pin "123") (pinfunction "123_123") (pintype "unspecified"))
      (node (ref "U11") (pin "124") (pinfunction "124_124") (pintype "unspecified"))
      (node (ref "U11") (pin "129") (pinfunction "129_129") (pintype "unspecified"))
      (node (ref "U11") (pin "130") (pinfunction "130_130") (pintype "unspecified"))
      (node (ref "U11") (pin "135") (pinfunction "135_135") (pintype "unspecified"))
      (node (ref "U11") (pin "136") (pinfunction "136_136") (pintype "unspecified"))
      (node (ref "U11") (pin "141") (pinfunction "141_141") (pintype "unspecified"))
      (node (ref "U11") (pin "142") (pinfunction "142_142") (pintype "unspecified"))
      (node (ref "U11") (pin "147") (pinfunction "147_147") (pintype "unspecified"))
      (node (ref "U11") (pin "148") (pinfunction "148_148") (pintype "unspecified"))
      (node (ref "U11") (pin "153") (pinfunction "153_153") (pintype "unspecified"))
      (node (ref "U11") (pin "154") (pinfunction "154_154") (pintype "unspecified"))
      (node (ref "U11") (pin "159") (pinfunction "159_159") (pintype "unspecified"))
      (node (ref "U11") (pin "160") (pinfunction "160_160") (pintype "unspecified"))
      (node (ref "U11") (pin "163") (pinfunction "163_163") (pintype "unspecified"))
      (node (ref "U3") (pin "1") (pinfunction "VCCA_1") (pintype "unspecified"))
      (node (ref "U3") (pin "2") (pinfunction "DIR_2") (pintype "unspecified"))
      (node (ref "U4") (pin "1") (pinfunction "VCCA_1") (pintype "unspecified"))
      (node (ref "U4") (pin "2") (pinfunction "DIR_2") (pintype "unspecified"))
      (node (ref "U5") (pin "1") (pinfunction "VCCA_1") (pintype "unspecified"))
      (node (ref "U5") (pin "2") (pinfunction "DIR_2") (pintype "unspecified"))
      (node (ref "U6") (pin "1") (pinfunction "VCCA_1") (pintype "unspecified"))
      (node (ref "U6") (pin "2") (pinfunction "DIR_2") (pintype "unspecified"))
      (node (ref "U6") (pin "3") (pinfunction "A1_3") (pintype "unspecified"))
      (node (ref "U7") (pin "1") (pinfunction "VCCA_1") (pintype "unspecified"))
      (node (ref "U8") (pin "1") (pinfunction "VCCA_1") (pintype "unspecified"))
      (node (ref "U9") (pin "3") (pinfunction "Vin_3") (pintype "unspecified"))
    )
    (net (code "108") (name "VDD") (class "Default")
      (node (ref "C12") (pin "1") (pinfunction "1_1") (pintype "unspecified"))
      (node (ref "C13") (pin "1") (pinfunction "1_1") (pintype "unspecified"))
      (node (ref "C15") (pin "1") (pinfunction "1_1") (pintype "unspecified"))
      (node (ref "C17") (pin "1") (pinfunction "1_1") (pintype "unspecified"))
      (node (ref "C18") (pin "1") (pinfunction "1_1") (pintype "unspecified"))
      (node (ref "C3") (pin "1") (pinfunction "1_1") (pintype "unspecified"))
      (node (ref "C4") (pin "1") (pinfunction "1_1") (pintype "unspecified"))
      (node (ref "C5") (pin "1") (pinfunction "1_1") (pintype "unspecified"))
      (node (ref "C6") (pin "1") (pinfunction "1_1") (pintype "unspecified"))
      (node (ref "C7") (pin "1") (pinfunction "1_1") (pintype "unspecified"))
      (node (ref "C8") (pin "1") (pinfunction "1_1") (pintype "unspecified"))
      (node (ref "U1") (pin "A6") (pinfunction "ZZ#_A6") (pintype "unspecified"))
      (node (ref "U1") (pin "D6") (pinfunction "VDD_D6") (pintype "unspecified"))
      (node (ref "U1") (pin "E1") (pinfunction "VDDQ_E1") (pintype "unspecified"))
      (node (ref "U2") (pin "A6") (pinfunction "ZZ#_A6") (pintype "unspecified"))
      (node (ref "U2") (pin "D6") (pinfunction "VDD_D6") (pintype "unspecified"))
      (node (ref "U2") (pin "E1") (pinfunction "VDDQ_E1") (pintype "unspecified"))
      (node (ref "U3") (pin "23") (pinfunction "VCCB_23") (pintype "unspecified"))
      (node (ref "U3") (pin "24") (pinfunction "VCCB_24") (pintype "unspecified"))
      (node (ref "U4") (pin "23") (pinfunction "VCCB_23") (pintype "unspecified"))
      (node (ref "U4") (pin "24") (pinfunction "VCCB_24") (pintype "unspecified"))
      (node (ref "U5") (pin "23") (pinfunction "VCCB_23") (pintype "unspecified"))
      (node (ref "U5") (pin "24") (pinfunction "VCCB_24") (pintype "unspecified"))
      (node (ref "U6") (pin "23") (pinfunction "VCCB_23") (pintype "unspecified"))
      (node (ref "U6") (pin "24") (pinfunction "VCCB_24") (pintype "unspecified"))
      (node (ref "U7") (pin "23") (pinfunction "VCCB_23") (pintype "unspecified"))
      (node (ref "U7") (pin "24") (pinfunction "VCCB_24") (pintype "unspecified"))
      (node (ref "U8") (pin "23") (pinfunction "VCCB_23") (pintype "unspecified"))
      (node (ref "U8") (pin "24") (pinfunction "VCCB_24") (pintype "unspecified"))
      (node (ref "U9") (pin "2") (pinfunction "Vout_2") (pintype "unspecified"))
      (node (ref "U9") (pin "4") (pinfunction "Vout_4") (pintype "unspecified"))
    )
    (net (code "109") (name "unconnected-(U6-B1-Pad21)") (class "Default")
      (node (ref "U6") (pin "21") (pinfunction "B1_21") (pintype "unspecified+no_connect"))
    )
    (net (code "110") (name "unconnected-(U6-B6-Pad16)") (class "Default")
      (node (ref "U6") (pin "16") (pinfunction "B6_16") (pintype "unspecified+no_connect"))
    )
    (net (code "111") (name "unconnected-(U6-B7-Pad15)") (class "Default")
      (node (ref "U6") (pin "15") (pinfunction "B7_15") (pintype "unspecified+no_connect"))
    )
    (net (code "112") (name "unconnected-(U6-B8-Pad14)") (class "Default")
      (node (ref "U6") (pin "14") (pinfunction "B8_14") (pintype "unspecified+no_connect"))
    )
    (net (code "113") (name "unconnected-(U11-Pad3)") (class "Default")
      (node (ref "U11") (pin "3") (pinfunction "3_3") (pintype "unspecified"))
    )
    (net (code "114") (name "unconnected-(U11-Pad4)") (class "Default")
      (node (ref "U11") (pin "4") (pinfunction "4_4") (pintype "unspecified"))
    )
    (net (code "115") (name "unconnected-(U11-Pad7)") (class "Default")
      (node (ref "U11") (pin "7") (pinfunction "7_7") (pintype "unspecified"))
    )
    (net (code "116") (name "unconnected-(U11-Pad28)") (class "Default")
      (node (ref "U11") (pin "28") (pinfunction "28_28") (pintype "unspecified"))
    )
    (net (code "117") (name "unconnected-(U11-Pad29)") (class "Default")
      (node (ref "U11") (pin "29") (pinfunction "29_29") (pintype "unspecified"))
    )
    (net (code "118") (name "unconnected-(U11-Pad32)") (class "Default")
      (node (ref "U11") (pin "32") (pinfunction "32_32") (pintype "unspecified"))
    )
    (net (code "119") (name "unconnected-(U11-Pad33)") (class "Default")
      (node (ref "U11") (pin "33") (pinfunction "33_33") (pintype "unspecified"))
    )
    (net (code "120") (name "unconnected-(U11-Pad34)") (class "Default")
      (node (ref "U11") (pin "34") (pinfunction "34_34") (pintype "unspecified"))
    )
    (net (code "121") (name "unconnected-(U11-Pad37)") (class "Default")
      (node (ref "U11") (pin "37") (pinfunction "37_37") (pintype "unspecified"))
    )
    (net (code "122") (name "unconnected-(U11-Pad38)") (class "Default")
      (node (ref "U11") (pin "38") (pinfunction "38_38") (pintype "unspecified"))
    )
    (net (code "123") (name "unconnected-(U11-Pad41)") (class "Default")
      (node (ref "U11") (pin "41") (pinfunction "41_41") (pintype "unspecified"))
    )
    (net (code "124") (name "unconnected-(U11-Pad42)") (class "Default")
      (node (ref "U11") (pin "42") (pinfunction "42_42") (pintype "unspecified"))
    )
    (net (code "125") (name "unconnected-(U11-Pad45)") (class "Default")
      (node (ref "U11") (pin "45") (pinfunction "45_45") (pintype "unspecified"))
    )
    (net (code "126") (name "unconnected-(U11-Pad63)") (class "Default")
      (node (ref "U11") (pin "63") (pinfunction "63_63") (pintype "unspecified+no_connect"))
    )
    (net (code "127") (name "unconnected-(U11-Pad66)") (class "Default")
      (node (ref "U11") (pin "66") (pinfunction "66_66") (pintype "unspecified+no_connect"))
    )
    (net (code "128") (name "unconnected-(U11-Pad67)") (class "Default")
      (node (ref "U11") (pin "67") (pinfunction "67_67") (pintype "unspecified+no_connect"))
    )
    (net (code "129") (name "unconnected-(U11-Pad71)") (class "Default")
      (node (ref "U11") (pin "71") (pinfunction "71_71") (pintype "unspecified+no_connect"))
    )
    (net (code "130") (name "unconnected-(U11-Pad74)") (class "Default")
      (node (ref "U11") (pin "74") (pinfunction "74_74") (pintype "unspecified+no_connect"))
    )
    (net (code "131") (name "unconnected-(U11-Pad75)") (class "Default")
      (node (ref "U11") (pin "75") (pinfunction "75_75") (pintype "unspecified+no_connect"))
    )
    (net (code "132") (name "unconnected-(U11-Pad76)") (class "Default")
      (node (ref "U11") (pin "76") (pinfunction "76_76") (pintype "unspecified+no_connect"))
    )
    (net (code "133") (name "unconnected-(U11-Pad79)") (class "Default")
      (node (ref "U11") (pin "79") (pinfunction "79_79") (pintype "unspecified+no_connect"))
    )
    (net (code "134") (name "unconnected-(U11-Pad80)") (class "Default")
      (node (ref "U11") (pin "80") (pinfunction "80_80") (pintype "unspecified+no_connect"))
    )
    (net (code "135") (name "unconnected-(U11-Pad84)") (class "Default")
      (node (ref "U11") (pin "84") (pinfunction "84_84") (pintype "unspecified+no_connect"))
    )
    (net (code "136") (name "unconnected-(U11-Pad87)") (class "Default")
      (node (ref "U11") (pin "87") (pinfunction "87_87") (pintype "unspecified+no_connect"))
    )
    (net (code "137") (name "unconnected-(U11-Pad92)") (class "Default")
      (node (ref "U11") (pin "92") (pinfunction "92_92") (pintype "unspecified+no_connect"))
    )
    (net (code "138") (name "unconnected-(U11-Pad96)") (class "Default")
      (node (ref "U11") (pin "96") (pinfunction "96_96") (pintype "unspecified+no_connect"))
    )
    (net (code "139") (name "unconnected-(U11-Pad97)") (class "Default")
      (node (ref "U11") (pin "97") (pinfunction "97_97") (pintype "unspecified+no_connect"))
    )
    (net (code "140") (name "unconnected-(U11-Pad100)") (class "Default")
      (node (ref "U11") (pin "100") (pinfunction "100_100") (pintype "unspecified+no_connect"))
    )
    (net (code "141") (name "unconnected-(U11-Pad101)") (class "Default")
      (node (ref "U11") (pin "101") (pinfunction "101_101") (pintype "unspecified+no_connect"))
    )
    (net (code "142") (name "unconnected-(U11-Pad105)") (class "Default")
      (node (ref "U11") (pin "105") (pinfunction "105_105") (pintype "unspecified+no_connect"))
    )
    (net (code "143") (name "unconnected-(U11-Pad108)") (class "Default")
      (node (ref "U11") (pin "108") (pinfunction "108_108") (pintype "unspecified+no_connect"))
    )
    (net (code "144") (name "unconnected-(U11-Pad109)") (class "Default")
      (node (ref "U11") (pin "109") (pinfunction "109_109") (pintype "unspecified+no_connect"))
    )
    (net (code "145") (name "unconnected-(U11-Pad113)") (class "Default")
      (node (ref "U11") (pin "113") (pinfunction "113_113") (pintype "unspecified+no_connect"))
    )
    (net (code "146") (name "unconnected-(U11-Pad114)") (class "Default")
      (node (ref "U11") (pin "114") (pinfunction "114_114") (pintype "unspecified+no_connect"))
    )
    (net (code "147") (name "unconnected-(U11-Pad115)") (class "Default")
      (node (ref "U11") (pin "115") (pinfunction "115_115") (pintype "unspecified+no_connect"))
    )
    (net (code "148") (name "unconnected-(U11-Pad116)") (class "Default")
      (node (ref "U11") (pin "116") (pinfunction "116_116") (pintype "unspecified+no_connect"))
    )
    (net (code "149") (name "unconnected-(U11-Pad119)") (class "Default")
      (node (ref "U11") (pin "119") (pinfunction "119_119") (pintype "unspecified+no_connect"))
    )
    (net (code "150") (name "unconnected-(U11-Pad120)") (class "Default")
      (node (ref "U11") (pin "120") (pinfunction "120_120") (pintype "unspecified+no_connect"))
    )
    (net (code "151") (name "unconnected-(U11-Pad122)") (class "Default")
      (node (ref "U11") (pin "122") (pinfunction "122_122") (pintype "unspecified+no_connect"))
    )
    (net (code "152") (name "unconnected-(U11-Pad125)") (class "Default")
      (node (ref "U11") (pin "125") (pinfunction "125_125") (pintype "unspecified+no_connect"))
    )
    (net (code "153") (name "unconnected-(U11-Pad126)") (class "Default")
      (node (ref "U11") (pin "126") (pinfunction "126_126") (pintype "unspecified+no_connect"))
    )
    (net (code "154") (name "unconnected-(U11-Pad143)") (class "Default")
      (node (ref "U11") (pin "143") (pinfunction "143_143") (pintype "unspecified+no_connect"))
    )
    (net (code "155") (name "unconnected-(U11-Pad144)") (class "Default")
      (node (ref "U11") (pin "144") (pinfunction "144_144") (pintype "unspecified+no_connect"))
    )
    (net (code "156") (name "unconnected-(U11-Pad145)") (class "Default")
      (node (ref "U11") (pin "145") (pinfunction "145_145") (pintype "unspecified+no_connect"))
    )
    (net (code "157") (name "unconnected-(U11-Pad146)") (class "Default")
      (node (ref "U11") (pin "146") (pinfunction "146_146") (pintype "unspecified+no_connect"))
    )
    (net (code "158") (name "unconnected-(U11-Pad149)") (class "Default")
      (node (ref "U11") (pin "149") (pinfunction "149_149") (pintype "unspecified+no_connect"))
    )
    (net (code "159") (name "unconnected-(U11-Pad150)") (class "Default")
      (node (ref "U11") (pin "150") (pinfunction "150_150") (pintype "unspecified+no_connect"))
    )
    (net (code "160") (name "unconnected-(U11-Pad151)") (class "Default")
      (node (ref "U11") (pin "151") (pinfunction "151_151") (pintype "unspecified+no_connect"))
    )
    (net (code "161") (name "unconnected-(U11-Pad152)") (class "Default")
      (node (ref "U11") (pin "152") (pinfunction "152_152") (pintype "unspecified+no_connect"))
    )
    (net (code "162") (name "unconnected-(U11-Pad155)") (class "Default")
      (node (ref "U11") (pin "155") (pinfunction "155_155") (pintype "unspecified+no_connect"))
    )
    (net (code "163") (name "unconnected-(U11-Pad156)") (class "Default")
      (node (ref "U11") (pin "156") (pinfunction "156_156") (pintype "unspecified+no_connect"))
    )
    (net (code "164") (name "unconnected-(U11-Pad161)") (class "Default")
      (node (ref "U11") (pin "161") (pinfunction "161_161") (pintype "unspecified+no_connect"))
    )
    (net (code "165") (name "unconnected-(U11-Pad177)") (class "Default")
      (node (ref "U11") (pin "177") (pinfunction "177_177") (pintype "unspecified+no_connect"))
    )
    (net (code "166") (name "unconnected-(U11-Pad178)") (class "Default")
      (node (ref "U11") (pin "178") (pinfunction "178_178") (pintype "unspecified+no_connect"))
    )
    (net (code "167") (name "unconnected-(U11-Pad179)") (class "Default")
      (node (ref "U11") (pin "179") (pinfunction "179_179") (pintype "unspecified+no_connect"))
    )
    (net (code "168") (name "unconnected-(U11-Pad182)") (class "Default")
      (node (ref "U11") (pin "182") (pinfunction "182_182") (pintype "unspecified+no_connect"))
    )
    (net (code "169") (name "unconnected-(U11-Pad183)") (class "Default")
      (node (ref "U11") (pin "183") (pinfunction "183_183") (pintype "unspecified+no_connect"))
    )
    (net (code "170") (name "unconnected-(U11-Pad186)") (class "Default")
      (node (ref "U11") (pin "186") (pinfunction "186_186") (pintype "unspecified+no_connect"))
    )
    (net (code "171") (name "unconnected-(U11-Pad187)") (class "Default")
      (node (ref "U11") (pin "187") (pinfunction "187_187") (pintype "unspecified+no_connect"))
    )
    (net (code "172") (name "unconnected-(U11-Pad190)") (class "Default")
      (node (ref "U11") (pin "190") (pinfunction "190_190") (pintype "unspecified+no_connect"))
    )
    (net (code "173") (name "unconnected-(U11-Pad191)") (class "Default")
      (node (ref "U11") (pin "191") (pinfunction "191_191") (pintype "unspecified+no_connect"))
    )
    (net (code "174") (name "unconnected-(U11-Pad194)") (class "Default")
      (node (ref "U11") (pin "194") (pinfunction "194_194") (pintype "unspecified+no_connect"))
    )
    (net (code "175") (name "unconnected-(U11-Pad211)") (class "Default")
      (node (ref "U11") (pin "211") (pinfunction "211_211") (pintype "unspecified"))
    )
    (net (code "176") (name "unconnected-(U11-Pad212)") (class "Default")
      (node (ref "U11") (pin "212") (pinfunction "212_212") (pintype "unspecified"))
    )
    (net (code "177") (name "unconnected-(U11-Pad215)") (class "Default")
      (node (ref "U11") (pin "215") (pinfunction "215_215") (pintype "unspecified"))
    )
    (net (code "178") (name "unconnected-(U11-Pad216)") (class "Default")
      (node (ref "U11") (pin "216") (pinfunction "216_216") (pintype "unspecified"))
    )
    (net (code "179") (name "unconnected-(U11-Pad219)") (class "Default")
      (node (ref "U11") (pin "219") (pinfunction "219_219") (pintype "unspecified"))
    )
    (net (code "180") (name "unconnected-(U11-Pad220)") (class "Default")
      (node (ref "U11") (pin "220") (pinfunction "220_220") (pintype "unspecified"))
    )
    (net (code "181") (name "unconnected-(U11-Pad221)") (class "Default")
      (node (ref "U11") (pin "221") (pinfunction "221_221") (pintype "unspecified"))
    )
    (net (code "182") (name "unconnected-(U11-Pad224)") (class "Default")
      (node (ref "U11") (pin "224") (pinfunction "224_224") (pintype "unspecified"))
    )
    (net (code "183") (name "unconnected-(U11-Pad225)") (class "Default")
      (node (ref "U11") (pin "225") (pinfunction "225_225") (pintype "unspecified"))
    )
    (net (code "184") (name "unconnected-(U11-Pad228)") (class "Default")
      (node (ref "U11") (pin "228") (pinfunction "228_228") (pintype "unspecified"))
    )
    (net (code "185") (name "unconnected-(U11-Pad229)") (class "Default")
      (node (ref "U11") (pin "229") (pinfunction "229_229") (pintype "unspecified"))
    )
    (net (code "186") (name "unconnected-(U11-Pad232)") (class "Default")
      (node (ref "U11") (pin "232") (pinfunction "232_232") (pintype "unspecified"))
    )
    (net (code "187") (name "unconnected-(U11-Pad249)") (class "Default")
      (node (ref "U11") (pin "249") (pinfunction "249_249") (pintype "unspecified"))
    )
    (net (code "188") (name "unconnected-(U11-Pad250)") (class "Default")
      (node (ref "U11") (pin "250") (pinfunction "250_250") (pintype "unspecified"))
    )
    (net (code "189") (name "unconnected-(U11-Pad253)") (class "Default")
      (node (ref "U11") (pin "253") (pinfunction "253_253") (pintype "unspecified"))
    )
    (net (code "190") (name "unconnected-(U11-Pad254)") (class "Default")
      (node (ref "U11") (pin "254") (pinfunction "254_254") (pintype "unspecified"))
    )
    (net (code "191") (name "unconnected-(U11-Pad255)") (class "Default")
      (node (ref "U11") (pin "255") (pinfunction "255_255") (pintype "unspecified"))
    )
    (net (code "192") (name "unconnected-(U11-Pad256)") (class "Default")
      (node (ref "U11") (pin "256") (pinfunction "256_256") (pintype "unspecified"))
    )
    (net (code "193") (name "unconnected-(U11-Pad257)") (class "Default")
      (node (ref "U11") (pin "257") (pinfunction "257_257") (pintype "unspecified"))
    )
    (net (code "194") (name "unconnected-(U11-Pad258)") (class "Default")
      (node (ref "U11") (pin "258") (pinfunction "258_258") (pintype "unspecified"))
    )
    (net (code "195") (name "unconnected-(U11-Pad259)") (class "Default")
      (node (ref "U11") (pin "259") (pinfunction "259_259") (pintype "unspecified"))
    )
    (net (code "196") (name "unconnected-(U11-Pad260)") (class "Default")
      (node (ref "U11") (pin "260") (pinfunction "260_260") (pintype "unspecified"))
    )
  )
)
